# power.net
KiCad netlist of a schematic drawn in Altium Designer
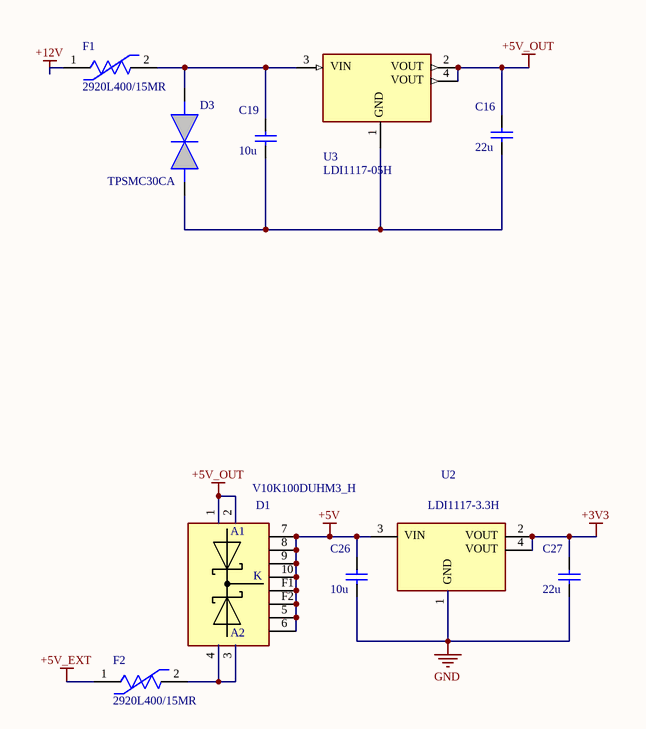
[diagram p0: power.SchDoc]

(export (version "E")
  (design (tool "Eeschema 10.0.6"))
  (components
    (comp (ref "C16")
      (value "22u")
      (footprint "CAPC1206(3216)150_L")
      (description "CAP 1.8uF 10V ±5% 1206 (3216 Metric) Thickness 1.45mm SMD")
      (fields (field (name "TOLERANCE") "Â±5%"))
      (libsource (lib "Altium Content Vault") (part "CAP"))
    )
    (comp (ref "C19")
      (value "10u")
      (footprint "CAPC1206(3216)150_L")
      (description "CAP 1.8uF 10V ±5% 1206 (3216 Metric) Thickness 1.45mm SMD")
      (fields (field (name "TOLERANCE") "Â±5%"))
      (libsource (lib "Altium Content Vault") (part "CAP"))
    )
    (comp (ref "C26")
      (value "10u")
      (footprint "CAPC1206(3216)150_L")
      (description "CAP 1.8uF 10V ±5% 1206 (3216 Metric) Thickness 1.45mm SMD")
      (fields (field (name "TOLERANCE") "Â±5%"))
      (libsource (lib "Altium Content Vault") (part "CAP"))
    )
    (comp (ref "C27")
      (value "22u")
      (footprint "CAPC1206(3216)150_L")
      (description "CAP 1.8uF 10V ±5% 1206 (3216 Metric) Thickness 1.45mm SMD")
      (fields (field (name "TOLERANCE") "Â±5%"))
      (libsource (lib "Altium Content Vault") (part "CAP"))
    )
    (comp (ref "D1")
      (value "V10K100DUHM3_H")
      (footprint "V10K100DUHM3H")
      (description "Schottky Diodes & Rectifiers 10A 100V TMBS FlatPAK 5x6")
      (fields
        (field (name "MANUFACTURER_PART_NUMBER") "V10K100DUHM3/H")
        (field (name "MOUSER PART NUMBER") "78-V10K100DUHM3/H")
      )
      (libsource (lib "HydrogreenLibrary") (part "V10K100DUHM3_H"))
    )
    (comp (ref "D3")
      (value "TPSMC30CA")
      (footprint "TPSMC30CA")
      (description "TPSMC Series - Surface Mount, 1500W TVS Diode-AEC-Q101 Qualified, 25.6V, 41.4V, DO-214AB, RoHS")
      (fields
        (field (name "MANUFACTURER_PART_NUMBER") "VS-MBRS340-M3/9AT")
        (field (name "MOUSER PART NUMBER") "78-VS-MBRS340-M39AT")
      )
      (libsource (lib "HydrogreenLibrary") (part "TPSMC30CA"))
    )
    (comp (ref "F1")
      (value "2920L400/15MR")
      (footprint "FP-2920L400-15MR-MFG")
      (description "PTC RESET FUSE 15V 4A 2920")
      (libsource (lib "Altium Content Vault") (part "fc31388045fc42ab786d6d00b506e9f"))
    )
    (comp (ref "F2")
      (value "2920L400/15MR")
      (footprint "FP-2920L400-15MR-MFG")
      (description "PTC RESET FUSE 15V 4A 2920")
      (libsource (lib "Altium Content Vault") (part "fc31388045fc42ab786d6d00b506e9f"))
    )
    (comp (ref "U2")
      (value "LDI1117-3.3H")
      (footprint "LDI1117-3.3H")
      (description "Fixed Positive LDO Regulator")
      (fields (field (name "MANUFACTURER") "Diotec"))
      (libsource (lib "HydrogreenLibrary") (part "LDI1117-3.3H"))
    )
    (comp (ref "U3")
      (value "LDI1117-05H")
      (footprint "LDI1117-05H")
      (description "Fixed Positive LDO Regulator")
      (fields (field (name "MANUFACTURER") "Diotec"))
      (libsource (lib "HydrogreenLibrary") (part "LDI1117-05H"))
    )
  )
  (nets
    (net (code "1") (name "+3V3") (class "Default")
      (node (ref "C27") (pin "1") (pinfunction "1_1") (pintype "passive"))
      (node (ref "U2") (pin "2") (pintype "power_in"))
      (node (ref "U2") (pin "4") (pintype "power_in"))
    )
    (net (code "2") (name "+5V") (class "Default")
      (node (ref "C26") (pin "1") (pinfunction "1_1") (pintype "passive"))
      (node (ref "D1") (pin "10") (pintype "passive"))
      (node (ref "D1") (pin "5") (pintype "passive"))
      (node (ref "D1") (pin "6") (pintype "passive"))
      (node (ref "D1") (pin "7") (pintype "passive"))
      (node (ref "D1") (pin "8") (pintype "passive"))
      (node (ref "D1") (pin "9") (pintype "passive"))
      (node (ref "D1") (pin "F1") (pintype "passive"))
      (node (ref "D1") (pin "F2") (pintype "passive"))
      (node (ref "U2") (pin "3") (pintype "power_in"))
    )
    (net (code "3") (name "+5V_EXT") (class "Default")
      (node (ref "F2") (pin "1") (pinfunction "1_1") (pintype "passive"))
    )
    (net (code "4") (name "+5V_OUT") (class "Default")
      (node (ref "C16") (pin "1") (pinfunction "1_1") (pintype "passive"))
      (node (ref "D1") (pin "1") (pintype "passive"))
      (node (ref "D1") (pin "2") (pintype "passive"))
      (node (ref "U3") (pin "2") (pintype "output"))
      (node (ref "U3") (pin "4") (pintype "output"))
    )
    (net (code "5") (name "+12V") (class "Default")
      (node (ref "F1") (pin "1") (pinfunction "1_1") (pintype "passive"))
    )
    (net (code "6") (name "GND") (class "Default")
      (node (ref "C26") (pin "2") (pinfunction "2_2") (pintype "passive"))
      (node (ref "C27") (pin "2") (pinfunction "2_2") (pintype "passive"))
      (node (ref "U2") (pin "1") (pintype "passive"))
    )
    (net (code "7") (name "Net-(D1-Pad3)") (class "Default")
      (node (ref "D1") (pin "3") (pintype "passive"))
      (node (ref "D1") (pin "4") (pintype "passive"))
      (node (ref "F2") (pin "2") (pinfunction "2_2") (pintype "passive"))
    )
    (net (code "8") (name "Net-(D3-A)") (class "Default")
      (node (ref "C16") (pin "2") (pinfunction "2_2") (pintype "passive"))
      (node (ref "C19") (pin "2") (pinfunction "2_2") (pintype "passive"))
      (node (ref "D3") (pin "2") (pinfunction "A_2") (pintype "passive"))
    )
    (net (code "9") (name "Net-(D3-K)") (class "Default")
      (node (ref "C19") (pin "1") (pinfunction "1_1") (pintype "passive"))
      (node (ref "D3") (pin "1") (pinfunction "K_1") (pintype "passive"))
      (node (ref "F1") (pin "2") (pinfunction "2_2") (pintype "passive"))
      (node (ref "U3") (pin "3") (pintype "input"))
    )
    (net (code "10") (name "unconnected-(U3-Pad1)") (class "Default")
      (node (ref "U3") (pin "1") (pintype "passive"))
    )
  )
)
